# Injector_2_0v.net
KiCad netlist of a schematic drawn in EAGLE
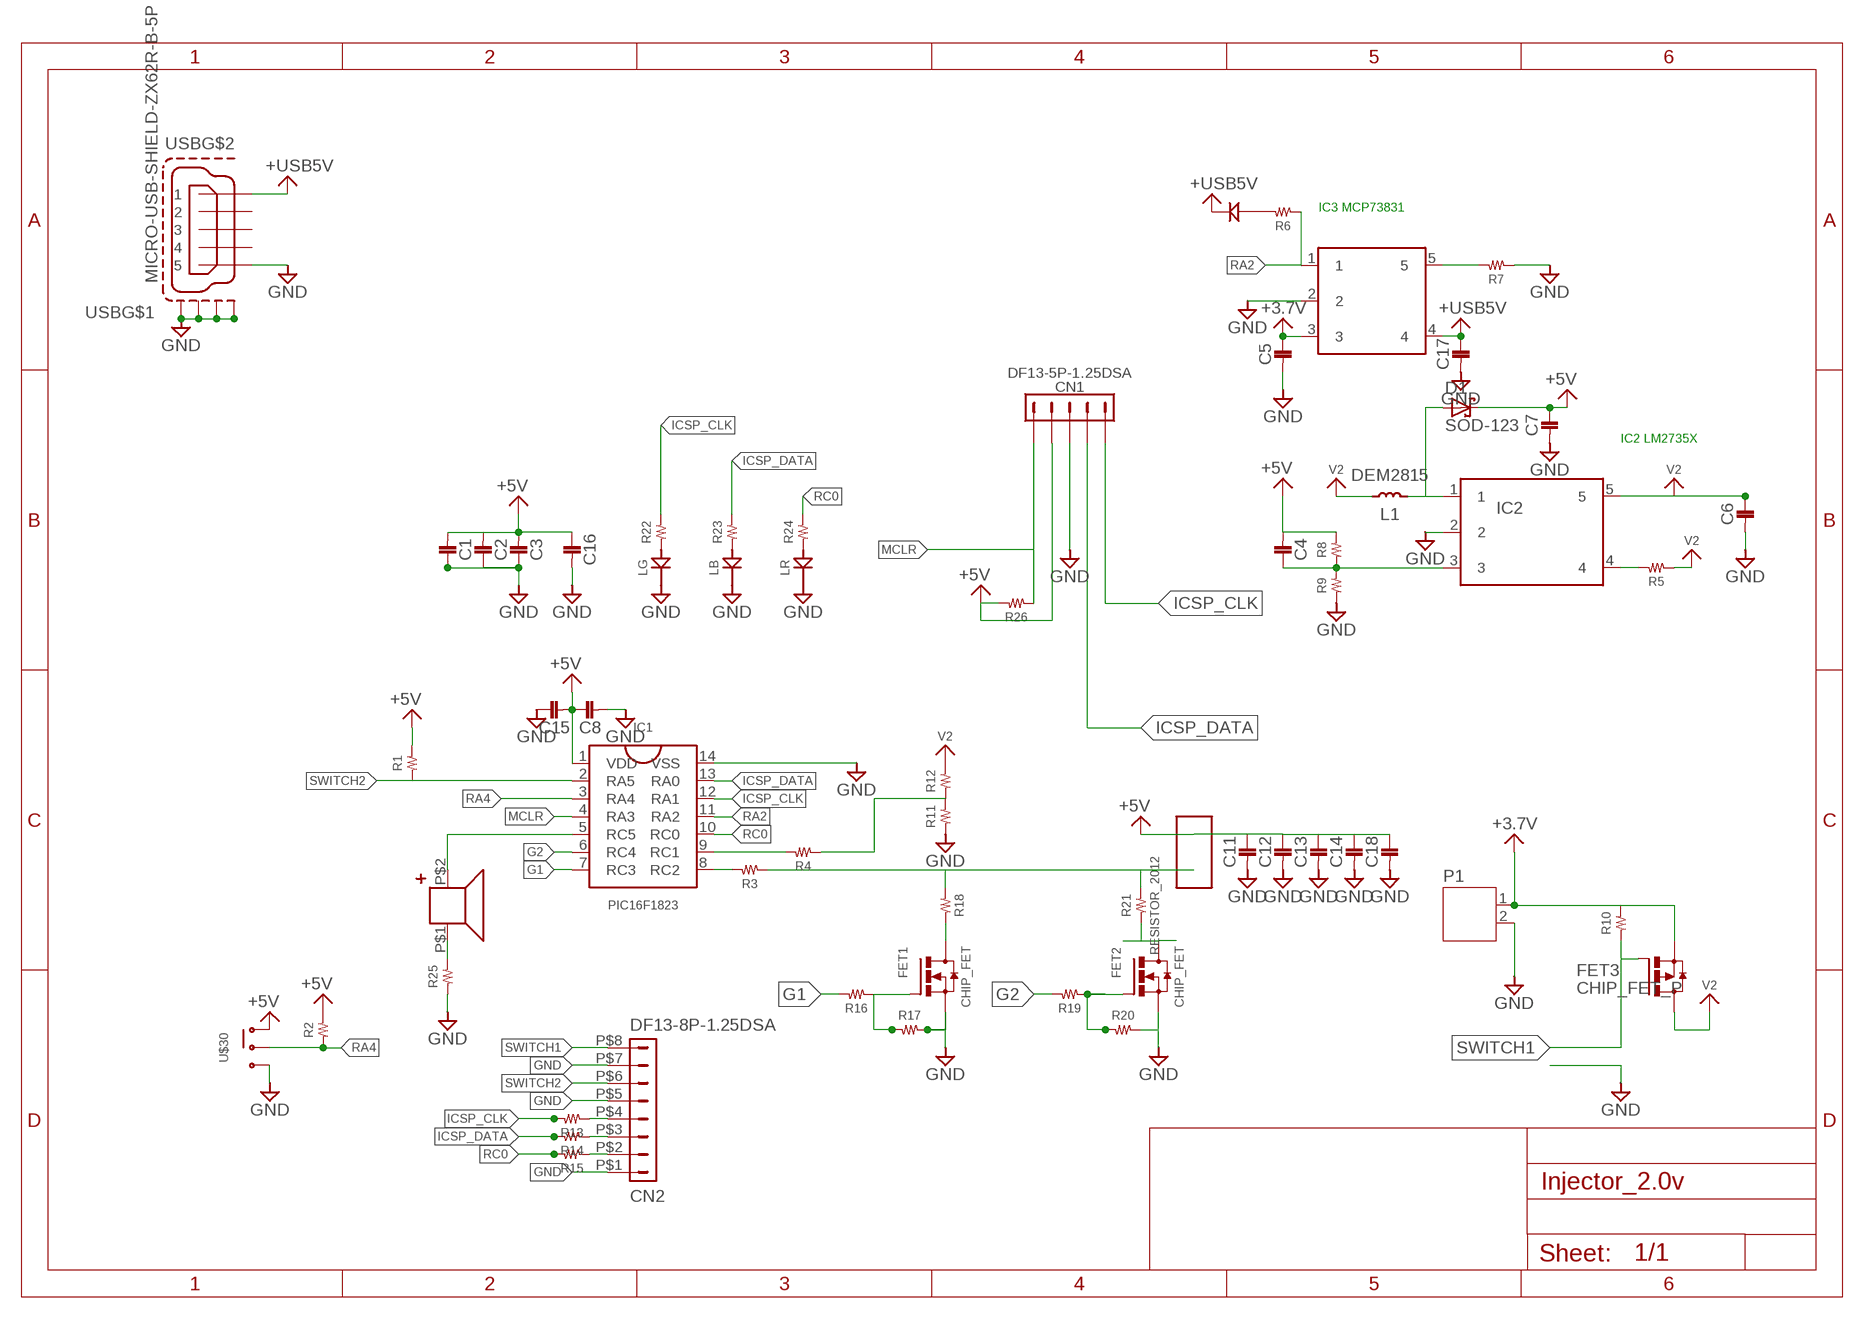
[diagram p0: schematic, sheet 1]

(export (version "E")
  (design (tool "Eeschema 10.0.6"))
  (components
    (comp (ref "C1")
      (value "1608")
      (footprint "eagle-import:1608")
      (libsource (lib "eagle-import") (part "1608"))
    )
    (comp (ref "C2")
      (value "1608")
      (footprint "eagle-import:1608")
      (libsource (lib "eagle-import") (part "1608"))
    )
    (comp (ref "C3")
      (value "1608")
      (footprint "eagle-import:1608")
      (libsource (lib "eagle-import") (part "1608"))
    )
    (comp (ref "C4")
      (value "1608")
      (footprint "eagle-import:1608")
      (libsource (lib "eagle-import") (part "1608"))
    )
    (comp (ref "C5")
      (value "1608")
      (footprint "eagle-import:1608")
      (libsource (lib "eagle-import") (part "1608"))
    )
    (comp (ref "C6")
      (value "1608")
      (footprint "eagle-import:1608")
      (libsource (lib "eagle-import") (part "1608"))
    )
    (comp (ref "C7")
      (value "1608")
      (footprint "eagle-import:1608")
      (libsource (lib "eagle-import") (part "1608"))
    )
    (comp (ref "C8")
      (value "1608")
      (footprint "eagle-import:1608")
      (libsource (lib "eagle-import") (part "1608"))
    )
    (comp (ref "C11")
      (value "1608")
      (footprint "eagle-import:1608")
      (libsource (lib "eagle-import") (part "1608"))
    )
    (comp (ref "C12")
      (value "1608")
      (footprint "eagle-import:1608")
      (libsource (lib "eagle-import") (part "1608"))
    )
    (comp (ref "C13")
      (value "1608")
      (footprint "eagle-import:1608")
      (libsource (lib "eagle-import") (part "1608"))
    )
    (comp (ref "C14")
      (value "1608")
      (footprint "eagle-import:1608")
      (libsource (lib "eagle-import") (part "1608"))
    )
    (comp (ref "C15")
      (value "1608")
      (footprint "eagle-import:1608")
      (libsource (lib "eagle-import") (part "1608"))
    )
    (comp (ref "C16")
      (value "1608")
      (footprint "eagle-import:1608")
      (libsource (lib "eagle-import") (part "1608"))
    )
    (comp (ref "C17")
      (value "1608")
      (footprint "eagle-import:1608")
      (libsource (lib "eagle-import") (part "1608"))
    )
    (comp (ref "C18")
      (value "1608")
      (footprint "eagle-import:1608")
      (libsource (lib "eagle-import") (part "1608"))
    )
    (comp (ref "CN1")
      (value "DF13-5P-1.25DSA")
      (footprint "eagle-import:DF13-5P-1.25DSA")
      (libsource (lib "eagle-import") (part "DF13-5P-1.25DSA"))
    )
    (comp (ref "CN2")
      (value "DF13-8P-1.25DSA")
      (footprint "eagle-import:DF13-8P-1.25DSA")
      (libsource (lib "eagle-import") (part "DF13-8P-1.25DSA"))
    )
    (comp (ref "D1")
      (value "SOD-123")
      (footprint "eagle-import:SOD_123")
      (libsource (lib "eagle-import") (part "SOD-123"))
    )
    (comp (ref "FET1")
      (value "CHIP_FET")
      (footprint "eagle-import:SOT23")
      (libsource (lib "eagle-import") (part "CHIP_FET"))
    )
    (comp (ref "FET2")
      (value "CHIP_FET")
      (footprint "eagle-import:SOT23")
      (libsource (lib "eagle-import") (part "CHIP_FET"))
    )
    (comp (ref "FET3")
      (value "CHIP_FET_P")
      (footprint "eagle-import:SOT23")
      (libsource (lib "eagle-import") (part "CHIP_FET_P"))
    )
    (comp (ref "IC1")
      (value "PIC16F1823")
      (footprint "eagle-import:TSSOP")
      (libsource (lib "eagle-import") (part "PIC16F1823"))
    )
    (comp (ref "IC2")
      (value "LM2735")
      (footprint "eagle-import:SOT23-5L")
      (libsource (lib "eagle-import") (part "LM2735"))
    )
    (comp (ref "IC3")
      (value "MCP73831")
      (footprint "eagle-import:SOT23-5L")
      (libsource (lib "eagle-import") (part "MCP73831"))
    )
    (comp (ref "L1")
      (value "DEM2815")
      (footprint "eagle-import:DEM2815")
      (libsource (lib "eagle-import") (part "DEM2815"))
    )
    (comp (ref "LB")
      (value "CHIPLED")
      (footprint "eagle-import:1608")
      (libsource (lib "eagle-import") (part "CHIPLED"))
    )
    (comp (ref "LG")
      (value "CHIPLED")
      (footprint "eagle-import:1608")
      (libsource (lib "eagle-import") (part "CHIPLED"))
    )
    (comp (ref "LR")
      (value "CHIPLED")
      (footprint "eagle-import:1608")
      (libsource (lib "eagle-import") (part "CHIPLED"))
    )
    (comp (ref "P1")
      (value "JST-PH2")
      (footprint "eagle-import:JST-PH2")
      (libsource (lib "eagle-import") (part "JST-PH2"))
    )
    (comp (ref "R1")
      (value "RESISTOR__SMD")
      (footprint "eagle-import:1608")
      (libsource (lib "eagle-import") (part "RESISTOR__SMD"))
    )
    (comp (ref "R2")
      (value "RESISTOR__SMD")
      (footprint "eagle-import:1608")
      (libsource (lib "eagle-import") (part "RESISTOR__SMD"))
    )
    (comp (ref "R3")
      (value "RESISTOR__SMD")
      (footprint "eagle-import:1608")
      (libsource (lib "eagle-import") (part "RESISTOR__SMD"))
    )
    (comp (ref "R4")
      (value "RESISTOR__SMD")
      (footprint "eagle-import:1608")
      (libsource (lib "eagle-import") (part "RESISTOR__SMD"))
    )
    (comp (ref "R5")
      (value "RESISTOR__SMD")
      (footprint "eagle-import:1608")
      (libsource (lib "eagle-import") (part "RESISTOR__SMD"))
    )
    (comp (ref "R6")
      (value "RESISTOR__SMD")
      (footprint "eagle-import:1608")
      (libsource (lib "eagle-import") (part "RESISTOR__SMD"))
    )
    (comp (ref "R7")
      (value "RESISTOR__SMD")
      (footprint "eagle-import:1608")
      (libsource (lib "eagle-import") (part "RESISTOR__SMD"))
    )
    (comp (ref "R8")
      (value "RESISTOR__SMD")
      (footprint "eagle-import:1608")
      (libsource (lib "eagle-import") (part "RESISTOR__SMD"))
    )
    (comp (ref "R9")
      (value "RESISTOR__SMD")
      (footprint "eagle-import:1608")
      (libsource (lib "eagle-import") (part "RESISTOR__SMD"))
    )
    (comp (ref "R10")
      (value "RESISTOR__SMD")
      (footprint "eagle-import:1608")
      (libsource (lib "eagle-import") (part "RESISTOR__SMD"))
    )
    (comp (ref "R11")
      (value "RESISTOR__SMD")
      (footprint "eagle-import:1608")
      (libsource (lib "eagle-import") (part "RESISTOR__SMD"))
    )
    (comp (ref "R12")
      (value "RESISTOR__SMD")
      (footprint "eagle-import:1608")
      (libsource (lib "eagle-import") (part "RESISTOR__SMD"))
    )
    (comp (ref "R13")
      (value "RESISTOR__SMD")
      (footprint "eagle-import:1608")
      (libsource (lib "eagle-import") (part "RESISTOR__SMD"))
    )
    (comp (ref "R14")
      (value "RESISTOR__SMD")
      (footprint "eagle-import:1608")
      (libsource (lib "eagle-import") (part "RESISTOR__SMD"))
    )
    (comp (ref "R15")
      (value "RESISTOR__SMD")
      (footprint "eagle-import:1608")
      (libsource (lib "eagle-import") (part "RESISTOR__SMD"))
    )
    (comp (ref "R16")
      (value "RESISTOR__SMD")
      (footprint "eagle-import:1608")
      (libsource (lib "eagle-import") (part "RESISTOR__SMD"))
    )
    (comp (ref "R17")
      (value "RESISTOR__SMD")
      (footprint "eagle-import:1608")
      (libsource (lib "eagle-import") (part "RESISTOR__SMD"))
    )
    (comp (ref "R18")
      (value "RESISTOR__SMD")
      (footprint "eagle-import:1608")
      (libsource (lib "eagle-import") (part "RESISTOR__SMD"))
    )
    (comp (ref "R19")
      (value "RESISTOR__SMD")
      (footprint "eagle-import:1608")
      (libsource (lib "eagle-import") (part "RESISTOR__SMD"))
    )
    (comp (ref "R20")
      (value "RESISTOR__SMD")
      (footprint "eagle-import:1608")
      (libsource (lib "eagle-import") (part "RESISTOR__SMD"))
    )
    (comp (ref "R21")
      (value "RESISTOR_2012")
      (footprint "eagle-import:2012")
      (libsource (lib "eagle-import") (part "RESISTOR_2012"))
    )
    (comp (ref "R22")
      (value "RESISTOR__SMD")
      (footprint "eagle-import:1608")
      (libsource (lib "eagle-import") (part "RESISTOR__SMD"))
    )
    (comp (ref "R23")
      (value "RESISTOR__SMD")
      (footprint "eagle-import:1608")
      (libsource (lib "eagle-import") (part "RESISTOR__SMD"))
    )
    (comp (ref "R24")
      (value "RESISTOR__SMD")
      (footprint "eagle-import:1608")
      (libsource (lib "eagle-import") (part "RESISTOR__SMD"))
    )
    (comp (ref "R25")
      (value "RESISTOR__SMD")
      (footprint "eagle-import:1608")
      (libsource (lib "eagle-import") (part "RESISTOR__SMD"))
    )
    (comp (ref "R26")
      (value "RESISTOR__SMD")
      (footprint "eagle-import:1608")
      (libsource (lib "eagle-import") (part "RESISTOR__SMD"))
    )
    (comp (ref "ST")
      (value "1608")
      (footprint "eagle-import:1608")
      (libsource (lib "eagle-import") (part "10_LED_1608"))
    )
    (comp (ref "U$15")
      (value "PKLCS1212E4001")
      (footprint "eagle-import:PKLCS1212E4001")
      (libsource (lib "eagle-import") (part "PKLCS1212E4001"))
    )
    (comp (ref "U$16")
      (value "PIN_HEADER_2_LARGE")
      (footprint "eagle-import:PIN_HEADER_2S_LARGE")
      (libsource (lib "eagle-import") (part "PIN_HEADER_2_LARGE"))
    )
    (comp (ref "U$30")
      (value "SS12D01G4")
      (footprint "eagle-import:SS12D01G4")
      (libsource (lib "eagle-import") (part "SS12D01G4"))
    )
    (comp (ref "USB")
      (value "MICRO-USB-SHIELD-ZX62R-B-5P")
      (footprint "eagle-import:ZX62R-B-5P")
      (libsource (lib "eagle-import") (part "MICRO-USB-SHIELD-ZX62R-B-5P"))
    )
  )
  (nets
    (net (code "1") (name "+3.7V") (class "Default")
      (node (ref "C5") (pin "P$1") (pinfunction "1_P$1") (pintype "passive"))
      (node (ref "FET3") (pin "2") (pinfunction "S_2") (pintype "passive"))
      (node (ref "IC3") (pin "3") (pinfunction "3_3") (pintype "bidirectional"))
      (node (ref "P1") (pin "1") (pinfunction "1_1") (pintype "passive"))
      (node (ref "R10") (pin "2") (pinfunction "P$2_2") (pintype "passive"))
    )
    (net (code "2") (name "+5V") (class "Default")
      (node (ref "C1") (pin "P$2") (pinfunction "2_P$2") (pintype "passive"))
      (node (ref "C11") (pin "P$1") (pinfunction "1_P$1") (pintype "passive"))
      (node (ref "C12") (pin "P$1") (pinfunction "1_P$1") (pintype "passive"))
      (node (ref "C13") (pin "P$1") (pinfunction "1_P$1") (pintype "passive"))
      (node (ref "C14") (pin "P$1") (pinfunction "1_P$1") (pintype "passive"))
      (node (ref "C15") (pin "P$2") (pinfunction "2_P$2") (pintype "passive"))
      (node (ref "C16") (pin "P$1") (pinfunction "1_P$1") (pintype "passive"))
      (node (ref "C18") (pin "P$1") (pinfunction "1_P$1") (pintype "passive"))
      (node (ref "C2") (pin "P$2") (pinfunction "2_P$2") (pintype "passive"))
      (node (ref "C3") (pin "P$2") (pinfunction "2_P$2") (pintype "passive"))
      (node (ref "C4") (pin "P$2") (pinfunction "2_P$2") (pintype "passive"))
      (node (ref "C7") (pin "P$1") (pinfunction "1_P$1") (pintype "passive"))
      (node (ref "C8") (pin "P$1") (pinfunction "1_P$1") (pintype "passive"))
      (node (ref "CN1") (pin "P$2") (pinfunction "2_P$2") (pintype "passive"))
      (node (ref "D1") (pin "C") (pinfunction "C_C") (pintype "passive"))
      (node (ref "IC1") (pin "1") (pinfunction "VDD_1") (pintype "bidirectional"))
      (node (ref "R1") (pin "2") (pinfunction "P$2_2") (pintype "passive"))
      (node (ref "R2") (pin "2") (pinfunction "P$2_2") (pintype "passive"))
      (node (ref "R26") (pin "2") (pinfunction "P$2_2") (pintype "passive"))
      (node (ref "R8") (pin "2") (pinfunction "P$2_2") (pintype "passive"))
      (node (ref "U$16") (pin "P$2") (pinfunction "P$2_P$2") (pintype "bidirectional"))
      (node (ref "U$30") (pin "1") (pinfunction "P$1_1") (pintype "bidirectional"))
    )
    (net (code "3") (name "+USB5V") (class "Default")
      (node (ref "C17") (pin "P$1") (pinfunction "1_P$1") (pintype "passive"))
      (node (ref "IC3") (pin "4") (pinfunction "4_4") (pintype "bidirectional"))
      (node (ref "ST") (pin "2") (pinfunction "K_2") (pintype "bidirectional"))
      (node (ref "USB") (pin "1") (pinfunction "1_1") (pintype "input"))
    )
    (net (code "4") (name "G1") (class "Default")
      (node (ref "IC1") (pin "7") (pinfunction "RC3_7") (pintype "bidirectional"))
      (node (ref "R16") (pin "2") (pinfunction "P$2_2") (pintype "passive"))
    )
    (net (code "5") (name "G2") (class "Default")
      (node (ref "IC1") (pin "6") (pinfunction "RC4_6") (pintype "bidirectional"))
      (node (ref "R19") (pin "2") (pinfunction "P$2_2") (pintype "passive"))
    )
    (net (code "6") (name "GND") (class "Default")
      (node (ref "C1") (pin "P$1") (pinfunction "1_P$1") (pintype "passive"))
      (node (ref "C11") (pin "P$2") (pinfunction "2_P$2") (pintype "passive"))
      (node (ref "C12") (pin "P$2") (pinfunction "2_P$2") (pintype "passive"))
      (node (ref "C13") (pin "P$2") (pinfunction "2_P$2") (pintype "passive"))
      (node (ref "C14") (pin "P$2") (pinfunction "2_P$2") (pintype "passive"))
      (node (ref "C15") (pin "P$1") (pinfunction "1_P$1") (pintype "passive"))
      (node (ref "C16") (pin "P$2") (pinfunction "2_P$2") (pintype "passive"))
      (node (ref "C17") (pin "P$2") (pinfunction "2_P$2") (pintype "passive"))
      (node (ref "C18") (pin "P$2") (pinfunction "2_P$2") (pintype "passive"))
      (node (ref "C2") (pin "P$1") (pinfunction "1_P$1") (pintype "passive"))
      (node (ref "C3") (pin "P$1") (pinfunction "1_P$1") (pintype "passive"))
      (node (ref "C5") (pin "P$2") (pinfunction "2_P$2") (pintype "passive"))
      (node (ref "C6") (pin "P$2") (pinfunction "2_P$2") (pintype "passive"))
      (node (ref "C7") (pin "P$2") (pinfunction "2_P$2") (pintype "passive"))
      (node (ref "C8") (pin "P$2") (pinfunction "2_P$2") (pintype "passive"))
      (node (ref "CN1") (pin "P$3") (pinfunction "3_P$3") (pintype "passive"))
      (node (ref "CN2") (pin "P$1") (pinfunction "1_P$1") (pintype "passive"))
      (node (ref "CN2") (pin "P$5") (pinfunction "5_P$5") (pintype "passive"))
      (node (ref "CN2") (pin "P$7") (pinfunction "7_P$7") (pintype "passive"))
      (node (ref "FET1") (pin "2") (pinfunction "S_2") (pintype "passive"))
      (node (ref "FET2") (pin "2") (pinfunction "S_2") (pintype "passive"))
      (node (ref "IC1") (pin "14") (pinfunction "VSS_14") (pintype "bidirectional"))
      (node (ref "IC2") (pin "2") (pinfunction "2_2") (pintype "bidirectional"))
      (node (ref "IC3") (pin "2") (pinfunction "2_2") (pintype "bidirectional"))
      (node (ref "LB") (pin "2") (pinfunction "K_2") (pintype "bidirectional"))
      (node (ref "LG") (pin "2") (pinfunction "K_2") (pintype "bidirectional"))
      (node (ref "LR") (pin "2") (pinfunction "K_2") (pintype "bidirectional"))
      (node (ref "P1") (pin "2") (pinfunction "2_2") (pintype "passive"))
      (node (ref "R11") (pin "1") (pinfunction "P$1_1") (pintype "passive"))
      (node (ref "R17") (pin "2") (pinfunction "P$2_2") (pintype "passive"))
      (node (ref "R20") (pin "2") (pinfunction "P$2_2") (pintype "passive"))
      (node (ref "R25") (pin "1") (pinfunction "P$1_1") (pintype "passive"))
      (node (ref "R7") (pin "1") (pinfunction "P$1_1") (pintype "passive"))
      (node (ref "R9") (pin "1") (pinfunction "P$1_1") (pintype "passive"))
      (node (ref "U$30") (pin "3") (pinfunction "P$3_3") (pintype "bidirectional"))
      (node (ref "USB") (pin "5") (pinfunction "5_5") (pintype "input"))
      (node (ref "USB") (pin "M1") (pinfunction "S1_M1") (pintype "passive"))
      (node (ref "USB") (pin "M2") (pinfunction "S2_M2") (pintype "passive"))
      (node (ref "USB") (pin "M3") (pinfunction "S3_M3") (pintype "passive"))
      (node (ref "USB") (pin "M4") (pinfunction "S4_M4") (pintype "passive"))
    )
    (net (code "7") (name "ICSP_CLK") (class "Default")
      (node (ref "CN1") (pin "P$5") (pinfunction "5_P$5") (pintype "passive"))
      (node (ref "IC1") (pin "12") (pinfunction "RA1_12") (pintype "bidirectional"))
      (node (ref "R13") (pin "2") (pinfunction "P$2_2") (pintype "passive"))
      (node (ref "R22") (pin "2") (pinfunction "P$2_2") (pintype "passive"))
    )
    (net (code "8") (name "ICSP_DATA") (class "Default")
      (node (ref "CN1") (pin "P$4") (pinfunction "4_P$4") (pintype "passive"))
      (node (ref "IC1") (pin "13") (pinfunction "RA0_13") (pintype "bidirectional"))
      (node (ref "R14") (pin "2") (pinfunction "P$2_2") (pintype "passive"))
      (node (ref "R23") (pin "2") (pinfunction "P$2_2") (pintype "passive"))
    )
    (net (code "9") (name "MCLR") (class "Default")
      (node (ref "CN1") (pin "P$1") (pinfunction "1_P$1") (pintype "passive"))
      (node (ref "IC1") (pin "4") (pinfunction "RA3_4") (pintype "bidirectional"))
      (node (ref "R26") (pin "1") (pinfunction "P$1_1") (pintype "passive"))
    )
    (net (code "10") (name "Net-(C4-1)") (class "Default")
      (node (ref "C4") (pin "P$1") (pinfunction "1_P$1") (pintype "passive"))
      (node (ref "IC2") (pin "3") (pinfunction "3_3") (pintype "bidirectional"))
      (node (ref "R8") (pin "1") (pinfunction "P$1_1") (pintype "passive"))
      (node (ref "R9") (pin "2") (pinfunction "P$2_2") (pintype "passive"))
    )
    (net (code "11") (name "Net-(CN2-2)") (class "Default")
      (node (ref "CN2") (pin "P$2") (pinfunction "2_P$2") (pintype "passive"))
      (node (ref "R15") (pin "1") (pinfunction "P$1_1") (pintype "passive"))
    )
    (net (code "12") (name "Net-(CN2-3)") (class "Default")
      (node (ref "CN2") (pin "P$3") (pinfunction "3_P$3") (pintype "passive"))
      (node (ref "R14") (pin "1") (pinfunction "P$1_1") (pintype "passive"))
    )
    (net (code "13") (name "Net-(CN2-4)") (class "Default")
      (node (ref "CN2") (pin "P$4") (pinfunction "4_P$4") (pintype "passive"))
      (node (ref "R13") (pin "1") (pinfunction "P$1_1") (pintype "passive"))
    )
    (net (code "14") (name "Net-(FET1-D)") (class "Default")
      (node (ref "FET1") (pin "3") (pinfunction "D_3") (pintype "passive"))
      (node (ref "R18") (pin "2") (pinfunction "P$2_2") (pintype "passive"))
    )
    (net (code "15") (name "Net-(FET1-G)") (class "Default")
      (node (ref "FET1") (pin "1") (pinfunction "G_1") (pintype "passive"))
      (node (ref "R16") (pin "1") (pinfunction "P$1_1") (pintype "passive"))
      (node (ref "R17") (pin "1") (pinfunction "P$1_1") (pintype "passive"))
    )
    (net (code "16") (name "Net-(FET2-D)") (class "Default")
      (node (ref "FET2") (pin "3") (pinfunction "D_3") (pintype "passive"))
      (node (ref "R21") (pin "1") (pinfunction "P$1_1") (pintype "passive"))
    )
    (net (code "17") (name "Net-(FET2-G)") (class "Default")
      (node (ref "FET2") (pin "1") (pinfunction "G_1") (pintype "passive"))
      (node (ref "R19") (pin "1") (pinfunction "P$1_1") (pintype "passive"))
      (node (ref "R20") (pin "1") (pinfunction "P$1_1") (pintype "passive"))
    )
    (net (code "18") (name "Net-(IC1-RC1)") (class "Default")
      (node (ref "IC1") (pin "9") (pinfunction "RC1_9") (pintype "bidirectional"))
      (node (ref "R4") (pin "2") (pinfunction "P$2_2") (pintype "passive"))
    )
    (net (code "19") (name "Net-(IC1-RC2)") (class "Default")
      (node (ref "IC1") (pin "8") (pinfunction "RC2_8") (pintype "bidirectional"))
      (node (ref "R3") (pin "2") (pinfunction "P$2_2") (pintype "passive"))
    )
    (net (code "20") (name "Net-(IC1-RC5)") (class "Default")
      (node (ref "IC1") (pin "5") (pinfunction "RC5_5") (pintype "bidirectional"))
      (node (ref "U$15") (pin "P$2") (pinfunction "PLUS_P$2") (pintype "bidirectional"))
    )
    (net (code "21") (name "Net-(L1-2)") (class "Default")
      (node (ref "D1") (pin "A") (pinfunction "A_A") (pintype "passive"))
      (node (ref "IC2") (pin "1") (pinfunction "1_1") (pintype "bidirectional"))
      (node (ref "L1") (pin "P$2") (pinfunction "2_P$2") (pintype "passive"))
    )
    (net (code "22") (name "Net-(LB-A)") (class "Default")
      (node (ref "LB") (pin "1") (pinfunction "A_1") (pintype "bidirectional"))
      (node (ref "R23") (pin "1") (pinfunction "P$1_1") (pintype "passive"))
    )
    (net (code "23") (name "Net-(LG-A)") (class "Default")
      (node (ref "LG") (pin "1") (pinfunction "A_1") (pintype "bidirectional"))
      (node (ref "R22") (pin "1") (pinfunction "P$1_1") (pintype "passive"))
    )
    (net (code "24") (name "Net-(LR-A)") (class "Default")
      (node (ref "LR") (pin "1") (pinfunction "A_1") (pintype "bidirectional"))
      (node (ref "R24") (pin "1") (pinfunction "P$1_1") (pintype "passive"))
    )
    (net (code "25") (name "Net-(R5-P$2)") (class "Default")
      (node (ref "IC2") (pin "4") (pinfunction "4_4") (pintype "bidirectional"))
      (node (ref "R5") (pin "2") (pinfunction "P$2_2") (pintype "passive"))
    )
    (net (code "26") (name "Net-(R6-P$2)") (class "Default")
      (node (ref "R6") (pin "2") (pinfunction "P$2_2") (pintype "passive"))
      (node (ref "ST") (pin "1") (pinfunction "A_1") (pintype "bidirectional"))
    )
    (net (code "27") (name "Net-(R7-P$2)") (class "Default")
      (node (ref "IC3") (pin "5") (pinfunction "5_5") (pintype "bidirectional"))
      (node (ref "R7") (pin "2") (pinfunction "P$2_2") (pintype "passive"))
    )
    (net (code "28") (name "Net-(R11-P$2)") (class "Default")
      (node (ref "R11") (pin "2") (pinfunction "P$2_2") (pintype "passive"))
      (node (ref "R12") (pin "1") (pinfunction "P$1_1") (pintype "passive"))
      (node (ref "R4") (pin "1") (pinfunction "P$1_1") (pintype "passive"))
    )
    (net (code "29") (name "Net-(R18-P$1)") (class "Default")
      (node (ref "R18") (pin "1") (pinfunction "P$1_1") (pintype "passive"))
      (node (ref "R21") (pin "2") (pinfunction "P$2_2") (pintype "passive"))
      (node (ref "R3") (pin "1") (pinfunction "P$1_1") (pintype "passive"))
      (node (ref "U$16") (pin "P$1") (pinfunction "P$1_P$1") (pintype "bidirectional"))
    )
    (net (code "30") (name "Net-(R25-P$2)") (class "Default")
      (node (ref "R25") (pin "2") (pinfunction "P$2_2") (pintype "passive"))
      (node (ref "U$15") (pin "P$1") (pinfunction "MINUS_P$1") (pintype "bidirectional"))
    )
    (net (code "31") (name "RA2") (class "Default")
      (node (ref "IC1") (pin "11") (pinfunction "RA2_11") (pintype "bidirectional"))
      (node (ref "IC3") (pin "1") (pinfunction "1_1") (pintype "bidirectional"))
      (node (ref "R6") (pin "1") (pinfunction "P$1_1") (pintype "passive"))
    )
    (net (code "32") (name "RA4") (class "Default")
      (node (ref "IC1") (pin "3") (pinfunction "RA4_3") (pintype "bidirectional"))
      (node (ref "R2") (pin "1") (pinfunction "P$1_1") (pintype "passive"))
      (node (ref "U$30") (pin "2") (pinfunction "P$2_2") (pintype "bidirectional"))
    )
    (net (code "33") (name "RC0") (class "Default")
      (node (ref "IC1") (pin "10") (pinfunction "RC0_10") (pintype "bidirectional"))
      (node (ref "R15") (pin "2") (pinfunction "P$2_2") (pintype "passive"))
      (node (ref "R24") (pin "2") (pinfunction "P$2_2") (pintype "passive"))
    )
    (net (code "34") (name "SWITCH1") (class "Default")
      (node (ref "CN2") (pin "P$8") (pinfunction "8_P$8") (pintype "passive"))
      (node (ref "FET3") (pin "1") (pinfunction "G_1") (pintype "passive"))
      (node (ref "R10") (pin "1") (pinfunction "P$1_1") (pintype "passive"))
    )
    (net (code "35") (name "SWITCH2") (class "Default")
      (node (ref "CN2") (pin "P$6") (pinfunction "6_P$6") (pintype "passive"))
      (node (ref "IC1") (pin "2") (pinfunction "RA5_2") (pintype "bidirectional"))
      (node (ref "R1") (pin "1") (pinfunction "P$1_1") (pintype "passive"))
    )
    (net (code "36") (name "V2") (class "Default")
      (node (ref "C6") (pin "P$1") (pinfunction "1_P$1") (pintype "passive"))
      (node (ref "FET3") (pin "3") (pinfunction "D_3") (pintype "passive"))
      (node (ref "IC2") (pin "5") (pinfunction "5_5") (pintype "bidirectional"))
      (node (ref "L1") (pin "P$1") (pinfunction "1_P$1") (pintype "passive"))
      (node (ref "R12") (pin "2") (pinfunction "P$2_2") (pintype "passive"))
      (node (ref "R5") (pin "1") (pinfunction "P$1_1") (pintype "passive"))
    )
    (net (code "37") (name "unconnected-(USB-Pad2)") (class "Default")
      (node (ref "USB") (pin "2") (pinfunction "2_2") (pintype "input"))
    )
    (net (code "38") (name "unconnected-(USB-Pad3)") (class "Default")
      (node (ref "USB") (pin "3") (pinfunction "3_3") (pintype "input"))
    )
    (net (code "39") (name "unconnected-(USB-Pad4)") (class "Default")
      (node (ref "USB") (pin "4") (pinfunction "4_4") (pintype "input"))
    )
  )
)
